# G209B.net
KiCad netlist of a schematic drawn in EAGLE
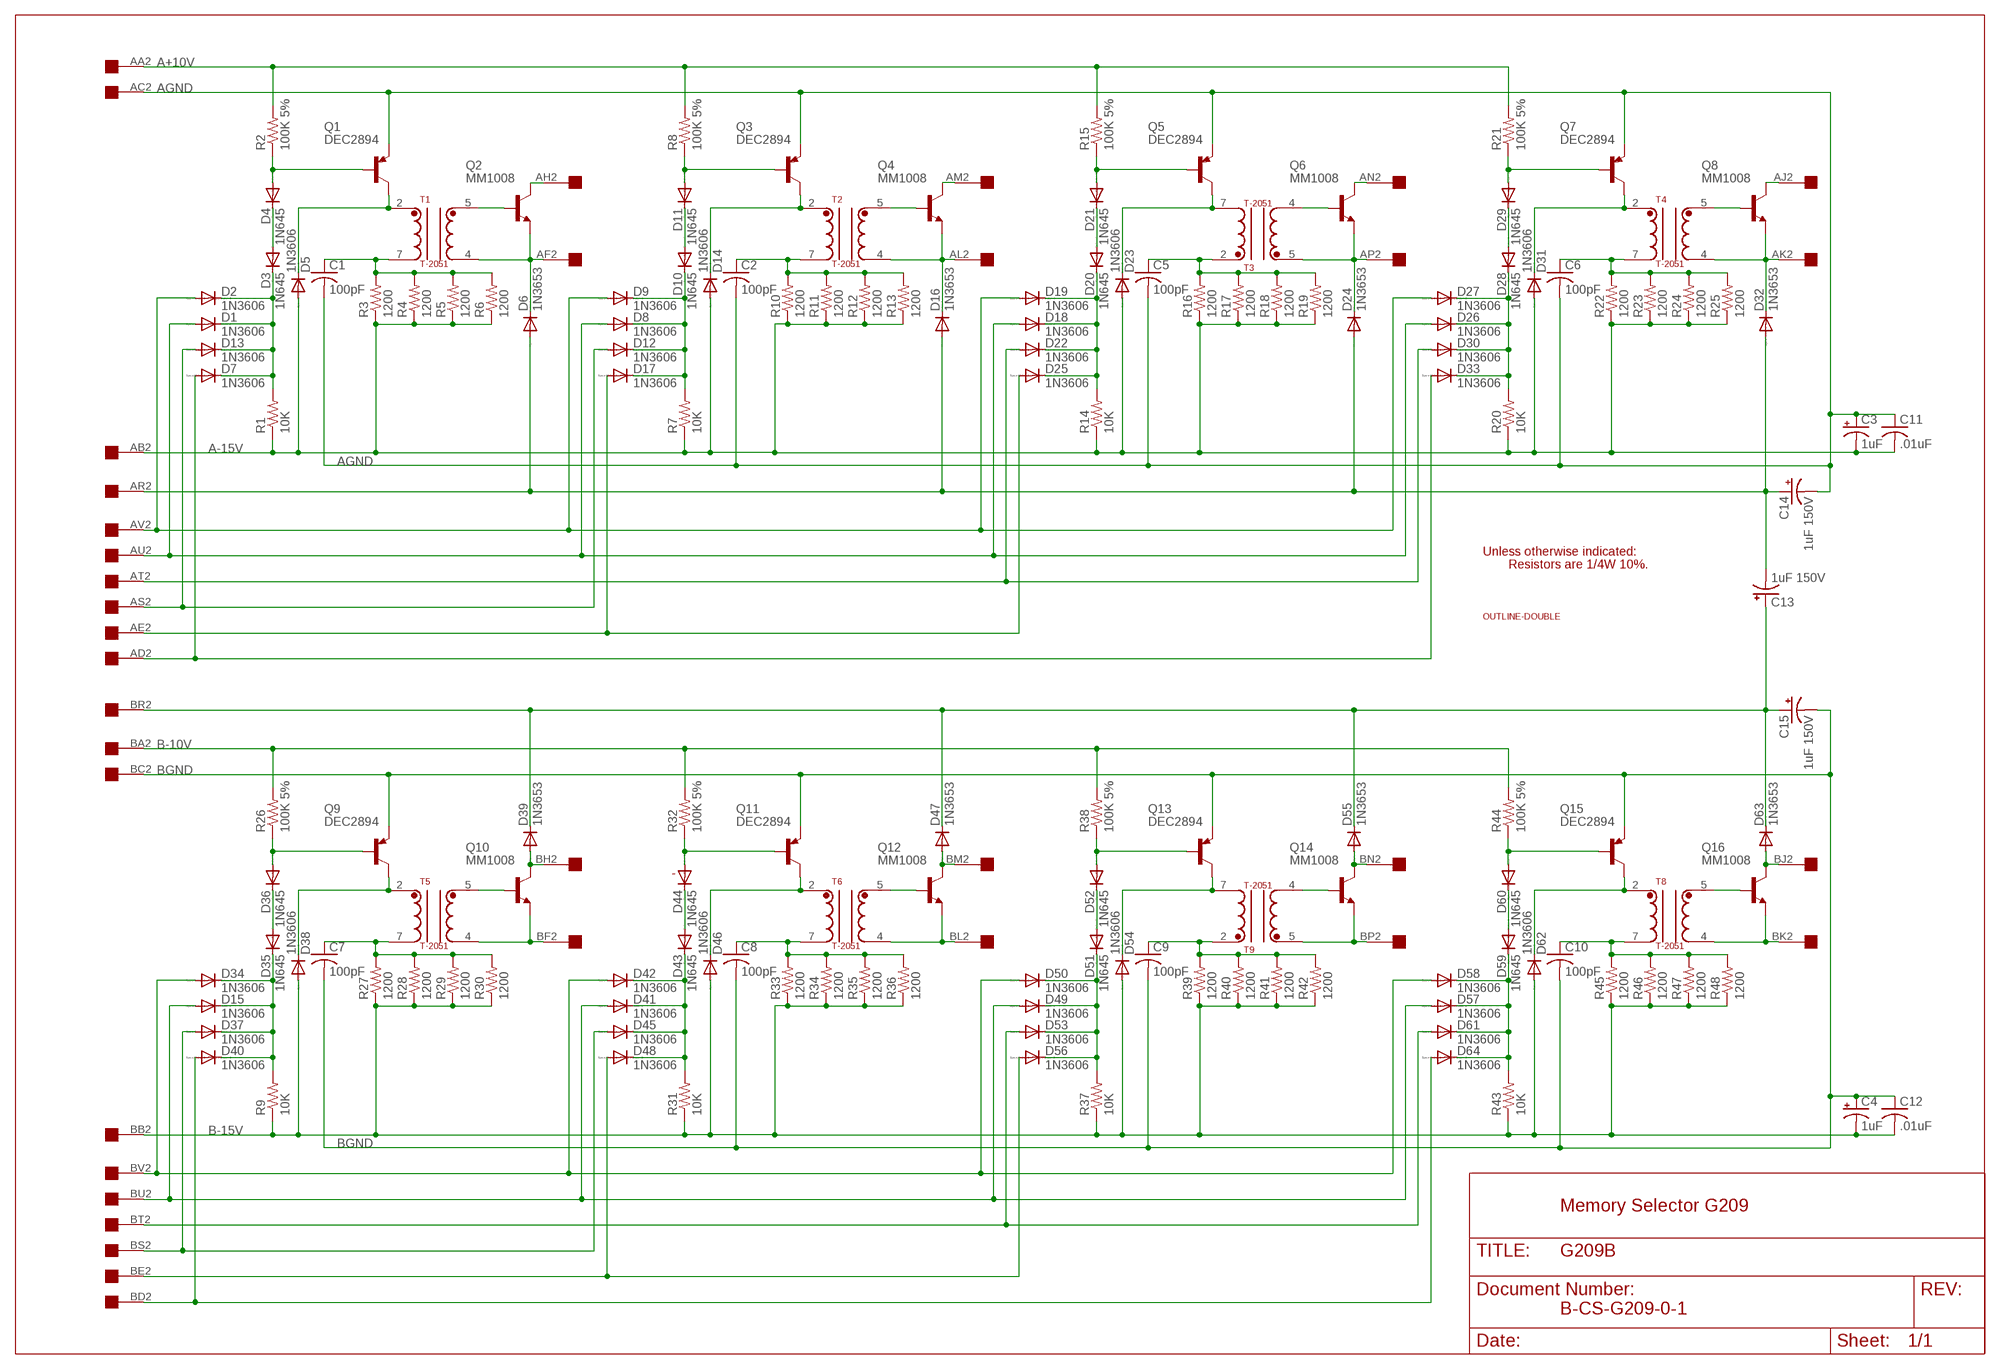
[diagram p0: schematic, sheet 1]

(export (version "E")
  (design (tool "Eeschema 10.0.6"))
  (components
    (comp (ref "C1")
      (value "100pF")
      (footprint "eagle-import:C075-032X103")
      (libsource (lib "eagle-import") (part "C-US075-032X103"))
    )
    (comp (ref "C2")
      (value "100pF")
      (footprint "eagle-import:C075-032X103")
      (libsource (lib "eagle-import") (part "C-US075-032X103"))
    )
    (comp (ref "C3")
      (value "1uF")
      (footprint "eagle-import:E12-4")
      (libsource (lib "eagle-import") (part "CPOL-USE12-4AXIAL"))
    )
    (comp (ref "C4")
      (value "1uF")
      (footprint "eagle-import:E12-4")
      (libsource (lib "eagle-import") (part "CPOL-USE12-4AXIAL"))
    )
    (comp (ref "C5")
      (value "100pF")
      (footprint "eagle-import:C075-032X103")
      (libsource (lib "eagle-import") (part "C-US075-032X103"))
    )
    (comp (ref "C6")
      (value "100pF")
      (footprint "eagle-import:C075-032X103")
      (libsource (lib "eagle-import") (part "C-US075-032X103"))
    )
    (comp (ref "C7")
      (value "100pF")
      (footprint "eagle-import:C075-032X103")
      (libsource (lib "eagle-import") (part "C-US075-032X103"))
    )
    (comp (ref "C8")
      (value "100pF")
      (footprint "eagle-import:C075-032X103")
      (libsource (lib "eagle-import") (part "C-US075-032X103"))
    )
    (comp (ref "C9")
      (value "100pF")
      (footprint "eagle-import:C075-032X103")
      (libsource (lib "eagle-import") (part "C-US075-032X103"))
    )
    (comp (ref "C10")
      (value "100pF")
      (footprint "eagle-import:C075-032X103")
      (libsource (lib "eagle-import") (part "C-US075-032X103"))
    )
    (comp (ref "C11")
      (value ".01uF")
      (footprint "eagle-import:C050-025X075")
      (libsource (lib "eagle-import") (part "C-US050-025X075"))
    )
    (comp (ref "C12")
      (value ".01uF")
      (footprint "eagle-import:C050-025X075")
      (libsource (lib "eagle-import") (part "C-US050-025X075"))
    )
    (comp (ref "C13")
      (value "1uF 150V")
      (footprint "eagle-import:E25-9")
      (libsource (lib "eagle-import") (part "CPOL-USE25-9AXIAL"))
    )
    (comp (ref "C14")
      (value "1uF 150V")
      (footprint "eagle-import:E25-9")
      (libsource (lib "eagle-import") (part "CPOL-USE25-9AXIAL"))
    )
    (comp (ref "C15")
      (value "1uF 150V")
      (footprint "eagle-import:E25-9")
      (libsource (lib "eagle-import") (part "CPOL-USE25-9AXIAL"))
    )
    (comp (ref "D1")
      (value "1N3606")
      (footprint "eagle-import:DO35-10")
      (libsource (lib "eagle-import") (part "1N4148DO35-10"))
    )
    (comp (ref "D2")
      (value "1N3606")
      (footprint "eagle-import:DO35-10")
      (libsource (lib "eagle-import") (part "1N4148DO35-10"))
    )
    (comp (ref "D3")
      (value "1N645")
      (footprint "eagle-import:DO35-10")
      (libsource (lib "eagle-import") (part "1N4148DO35-10"))
    )
    (comp (ref "D4")
      (value "1N645")
      (footprint "eagle-import:DO35-10")
      (libsource (lib "eagle-import") (part "1N4148DO35-10"))
    )
    (comp (ref "D5")
      (value "1N3606")
      (footprint "eagle-import:DO35-10")
      (libsource (lib "eagle-import") (part "1N4148DO35-10"))
    )
    (comp (ref "D6")
      (value "1N3653")
      (footprint "eagle-import:DO35-10")
      (libsource (lib "eagle-import") (part "1N4148DO35-10"))
    )
    (comp (ref "D7")
      (value "1N3606")
      (footprint "eagle-import:DO35-10")
      (libsource (lib "eagle-import") (part "1N4148DO35-10"))
    )
    (comp (ref "D8")
      (value "1N3606")
      (footprint "eagle-import:DO35-10")
      (libsource (lib "eagle-import") (part "1N4148DO35-10"))
    )
    (comp (ref "D9")
      (value "1N3606")
      (footprint "eagle-import:DO35-10")
      (libsource (lib "eagle-import") (part "1N4148DO35-10"))
    )
    (comp (ref "D10")
      (value "1N645")
      (footprint "eagle-import:DO35-10")
      (libsource (lib "eagle-import") (part "1N4148DO35-10"))
    )
    (comp (ref "D11")
      (value "1N645")
      (footprint "eagle-import:DO35-10")
      (libsource (lib "eagle-import") (part "1N4148DO35-10"))
    )
    (comp (ref "D12")
      (value "1N3606")
      (footprint "eagle-import:DO35-10")
      (libsource (lib "eagle-import") (part "1N4148DO35-10"))
    )
    (comp (ref "D13")
      (value "1N3606")
      (footprint "eagle-import:DO35-10")
      (libsource (lib "eagle-import") (part "1N4148DO35-10"))
    )
    (comp (ref "D14")
      (value "1N3606")
      (footprint "eagle-import:DO35-10")
      (libsource (lib "eagle-import") (part "1N4148DO35-10"))
    )
    (comp (ref "D15")
      (value "1N3606")
      (footprint "eagle-import:DO35-10")
      (libsource (lib "eagle-import") (part "1N4148DO35-10"))
    )
    (comp (ref "D16")
      (value "1N3653")
      (footprint "eagle-import:DO35-10")
      (libsource (lib "eagle-import") (part "1N4148DO35-10"))
    )
    (comp (ref "D17")
      (value "1N3606")
      (footprint "eagle-import:DO35-10")
      (libsource (lib "eagle-import") (part "1N4148DO35-10"))
    )
    (comp (ref "D18")
      (value "1N3606")
      (footprint "eagle-import:DO35-10")
      (libsource (lib "eagle-import") (part "1N4148DO35-10"))
    )
    (comp (ref "D19")
      (value "1N3606")
      (footprint "eagle-import:DO35-10")
      (libsource (lib "eagle-import") (part "1N4148DO35-10"))
    )
    (comp (ref "D20")
      (value "1N645")
      (footprint "eagle-import:DO35-10")
      (libsource (lib "eagle-import") (part "1N4148DO35-10"))
    )
    (comp (ref "D21")
      (value "1N645")
      (footprint "eagle-import:DO35-10")
      (libsource (lib "eagle-import") (part "1N4148DO35-10"))
    )
    (comp (ref "D22")
      (value "1N3606")
      (footprint "eagle-import:DO35-10")
      (libsource (lib "eagle-import") (part "1N4148DO35-10"))
    )
    (comp (ref "D23")
      (value "1N3606")
      (footprint "eagle-import:DO35-10")
      (libsource (lib "eagle-import") (part "1N4148DO35-10"))
    )
    (comp (ref "D24")
      (value "1N3653")
      (footprint "eagle-import:DO35-10")
      (libsource (lib "eagle-import") (part "1N4148DO35-10"))
    )
    (comp (ref "D25")
      (value "1N3606")
      (footprint "eagle-import:DO35-10")
      (libsource (lib "eagle-import") (part "1N4148DO35-10"))
    )
    (comp (ref "D26")
      (value "1N3606")
      (footprint "eagle-import:DO35-10")
      (libsource (lib "eagle-import") (part "1N4148DO35-10"))
    )
    (comp (ref "D27")
      (value "1N3606")
      (footprint "eagle-import:DO35-10")
      (libsource (lib "eagle-import") (part "1N4148DO35-10"))
    )
    (comp (ref "D28")
      (value "1N645")
      (footprint "eagle-import:DO35-10")
      (libsource (lib "eagle-import") (part "1N4148DO35-10"))
    )
    (comp (ref "D29")
      (value "1N645")
      (footprint "eagle-import:DO35-10")
      (libsource (lib "eagle-import") (part "1N4148DO35-10"))
    )
    (comp (ref "D30")
      (value "1N3606")
      (footprint "eagle-import:DO35-10")
      (libsource (lib "eagle-import") (part "1N4148DO35-10"))
    )
    (comp (ref "D31")
      (value "1N3606")
      (footprint "eagle-import:DO35-10")
      (libsource (lib "eagle-import") (part "1N4148DO35-10"))
    )
    (comp (ref "D32")
      (value "1N3653")
      (footprint "eagle-import:DO35-10")
      (libsource (lib "eagle-import") (part "1N4148DO35-10"))
    )
    (comp (ref "D33")
      (value "1N3606")
      (footprint "eagle-import:DO35-10")
      (libsource (lib "eagle-import") (part "1N4148DO35-10"))
    )
    (comp (ref "D34")
      (value "1N3606")
      (footprint "eagle-import:DO35-10")
      (libsource (lib "eagle-import") (part "1N4148DO35-10"))
    )
    (comp (ref "D35")
      (value "1N645")
      (footprint "eagle-import:DO35-10")
      (libsource (lib "eagle-import") (part "1N4148DO35-10"))
    )
    (comp (ref "D36")
      (value "1N645")
      (footprint "eagle-import:DO35-10")
      (libsource (lib "eagle-import") (part "1N4148DO35-10"))
    )
    (comp (ref "D37")
      (value "1N3606")
      (footprint "eagle-import:DO35-10")
      (libsource (lib "eagle-import") (part "1N4148DO35-10"))
    )
    (comp (ref "D38")
      (value "1N3606")
      (footprint "eagle-import:DO35-10")
      (libsource (lib "eagle-import") (part "1N4148DO35-10"))
    )
    (comp (ref "D39")
      (value "1N3653")
      (footprint "eagle-import:DO35-10")
      (libsource (lib "eagle-import") (part "1N4148DO35-10"))
    )
    (comp (ref "D40")
      (value "1N3606")
      (footprint "eagle-import:DO35-10")
      (libsource (lib "eagle-import") (part "1N4148DO35-10"))
    )
    (comp (ref "D41")
      (value "1N3606")
      (footprint "eagle-import:DO35-10")
      (libsource (lib "eagle-import") (part "1N4148DO35-10"))
    )
    (comp (ref "D42")
      (value "1N3606")
      (footprint "eagle-import:DO35-10")
      (libsource (lib "eagle-import") (part "1N4148DO35-10"))
    )
    (comp (ref "D43")
      (value "1N645")
      (footprint "eagle-import:DO35-10")
      (libsource (lib "eagle-import") (part "1N4148DO35-10"))
    )
    (comp (ref "D44")
      (value "1N645")
      (footprint "eagle-import:DO35-10")
      (libsource (lib "eagle-import") (part "1N4148DO35-10"))
    )
    (comp (ref "D45")
      (value "1N3606")
      (footprint "eagle-import:DO35-10")
      (libsource (lib "eagle-import") (part "1N4148DO35-10"))
    )
    (comp (ref "D46")
      (value "1N3606")
      (footprint "eagle-import:DO35-10")
      (libsource (lib "eagle-import") (part "1N4148DO35-10"))
    )
    (comp (ref "D47")
      (value "1N3653")
      (footprint "eagle-import:DO35-10")
      (libsource (lib "eagle-import") (part "1N4148DO35-10"))
    )
    (comp (ref "D48")
      (value "1N3606")
      (footprint "eagle-import:DO35-10")
      (libsource (lib "eagle-import") (part "1N4148DO35-10"))
    )
    (comp (ref "D49")
      (value "1N3606")
      (footprint "eagle-import:DO35-10")
      (libsource (lib "eagle-import") (part "1N4148DO35-10"))
    )
    (comp (ref "D50")
      (value "1N3606")
      (footprint "eagle-import:DO35-10")
      (libsource (lib "eagle-import") (part "1N4148DO35-10"))
    )
    (comp (ref "D51")
      (value "1N645")
      (footprint "eagle-import:DO35-10")
      (libsource (lib "eagle-import") (part "1N4148DO35-10"))
    )
    (comp (ref "D52")
      (value "1N645")
      (footprint "eagle-import:DO35-10")
      (libsource (lib "eagle-import") (part "1N4148DO35-10"))
    )
    (comp (ref "D53")
      (value "1N3606")
      (footprint "eagle-import:DO35-10")
      (libsource (lib "eagle-import") (part "1N4148DO35-10"))
    )
    (comp (ref "D54")
      (value "1N3606")
      (footprint "eagle-import:DO35-10")
      (libsource (lib "eagle-import") (part "1N4148DO35-10"))
    )
    (comp (ref "D55")
      (value "1N3653")
      (footprint "eagle-import:DO35-10")
      (libsource (lib "eagle-import") (part "1N4148DO35-10"))
    )
    (comp (ref "D56")
      (value "1N3606")
      (footprint "eagle-import:DO35-10")
      (libsource (lib "eagle-import") (part "1N4148DO35-10"))
    )
    (comp (ref "D57")
      (value "1N3606")
      (footprint "eagle-import:DO35-10")
      (libsource (lib "eagle-import") (part "1N4148DO35-10"))
    )
    (comp (ref "D58")
      (value "1N3606")
      (footprint "eagle-import:DO35-10")
      (libsource (lib "eagle-import") (part "1N4148DO35-10"))
    )
    (comp (ref "D59")
      (value "1N645")
      (footprint "eagle-import:DO35-10")
      (libsource (lib "eagle-import") (part "1N4148DO35-10"))
    )
    (comp (ref "D60")
      (value "1N645")
      (footprint "eagle-import:DO35-10")
      (libsource (lib "eagle-import") (part "1N4148DO35-10"))
    )
    (comp (ref "D61")
      (value "1N3606")
      (footprint "eagle-import:DO35-10")
      (libsource (lib "eagle-import") (part "1N4148DO35-10"))
    )
    (comp (ref "D62")
      (value "1N3606")
      (footprint "eagle-import:DO35-10")
      (libsource (lib "eagle-import") (part "1N4148DO35-10"))
    )
    (comp (ref "D63")
      (value "1N3653")
      (footprint "eagle-import:DO35-10")
      (libsource (lib "eagle-import") (part "1N4148DO35-10"))
    )
    (comp (ref "D64")
      (value "1N3606")
      (footprint "eagle-import:DO35-10")
      (libsource (lib "eagle-import") (part "1N4148DO35-10"))
    )
    (comp (ref "Q1")
      (value "DEC2894")
      (footprint "eagle-import:TO39")
      (libsource (lib "eagle-import") (part "2N2904"))
    )
    (comp (ref "Q2")
      (value "MM1008")
      (footprint "eagle-import:TO5")
      (libsource (lib "eagle-import") (part "2N2102"))
    )
    (comp (ref "Q3")
      (value "DEC2894")
      (footprint "eagle-import:TO39")
      (libsource (lib "eagle-import") (part "2N2904"))
    )
    (comp (ref "Q4")
      (value "MM1008")
      (footprint "eagle-import:TO5")
      (libsource (lib "eagle-import") (part "2N2102"))
    )
    (comp (ref "Q5")
      (value "DEC2894")
      (footprint "eagle-import:TO39")
      (libsource (lib "eagle-import") (part "2N2904"))
    )
    (comp (ref "Q6")
      (value "MM1008")
      (footprint "eagle-import:TO5")
      (libsource (lib "eagle-import") (part "2N2102"))
    )
    (comp (ref "Q7")
      (value "DEC2894")
      (footprint "eagle-import:TO39")
      (libsource (lib "eagle-import") (part "2N2904"))
    )
    (comp (ref "Q8")
      (value "MM1008")
      (footprint "eagle-import:TO5")
      (libsource (lib "eagle-import") (part "2N2102"))
    )
    (comp (ref "Q9")
      (value "DEC2894")
      (footprint "eagle-import:TO39")
      (libsource (lib "eagle-import") (part "2N2904"))
    )
    (comp (ref "Q10")
      (value "MM1008")
      (footprint "eagle-import:TO5")
      (libsource (lib "eagle-import") (part "2N2102"))
    )
    (comp (ref "Q11")
      (value "DEC2894")
      (footprint "eagle-import:TO39")
      (libsource (lib "eagle-import") (part "2N2904"))
    )
    (comp (ref "Q12")
      (value "MM1008")
      (footprint "eagle-import:TO5")
      (libsource (lib "eagle-import") (part "2N2102"))
    )
    (comp (ref "Q13")
      (value "DEC2894")
      (footprint "eagle-import:TO39")
      (libsource (lib "eagle-import") (part "2N2904"))
    )
    (comp (ref "Q14")
      (value "MM1008")
      (footprint "eagle-import:TO5")
      (libsource (lib "eagle-import") (part "2N2102"))
    )
    (comp (ref "Q15")
      (value "DEC2894")
      (footprint "eagle-import:TO39")
      (libsource (lib "eagle-import") (part "2N2904"))
    )
    (comp (ref "Q16")
      (value "MM1008")
      (footprint "eagle-import:TO5")
      (libsource (lib "eagle-import") (part "2N2102"))
    )
    (comp (ref "R1")
      (value "10K")
      (footprint "eagle-import:0207_10")
      (libsource (lib "eagle-import") (part "R-US_0207/10"))
    )
    (comp (ref "R2")
      (value "100K 5%")
      (footprint "eagle-import:0207_10")
      (libsource (lib "eagle-import") (part "R-US_0207/10"))
    )
    (comp (ref "R3")
      (value "1200")
      (footprint "eagle-import:0207_10")
      (libsource (lib "eagle-import") (part "R-US_0207/10"))
    )
    (comp (ref "R4")
      (value "1200")
      (footprint "eagle-import:0207_10")
      (libsource (lib "eagle-import") (part "R-US_0207/10"))
    )
    (comp (ref "R5")
      (value "1200")
      (footprint "eagle-import:0207_10")
      (libsource (lib "eagle-import") (part "R-US_0207/10"))
    )
    (comp (ref "R6")
      (value "1200")
      (footprint "eagle-import:0207_10")
      (libsource (lib "eagle-import") (part "R-US_0207/10"))
    )
    (comp (ref "R7")
      (value "10K")
      (footprint "eagle-import:0207_10")
      (libsource (lib "eagle-import") (part "R-US_0207/10"))
    )
    (comp (ref "R8")
      (value "100K 5%")
      (footprint "eagle-import:0207_10")
      (libsource (lib "eagle-import") (part "R-US_0207/10"))
    )
    (comp (ref "R9")
      (value "10K")
      (footprint "eagle-import:0207_10")
      (libsource (lib "eagle-import") (part "R-US_0207/10"))
    )
    (comp (ref "R10")
      (value "1200")
      (footprint "eagle-import:0207_10")
      (libsource (lib "eagle-import") (part "R-US_0207/10"))
    )
    (comp (ref "R11")
      (value "1200")
      (footprint "eagle-import:0207_10")
      (libsource (lib "eagle-import") (part "R-US_0207/10"))
    )
    (comp (ref "R12")
      (value "1200")
      (footprint "eagle-import:0207_10")
      (libsource (lib "eagle-import") (part "R-US_0207/10"))
    )
    (comp (ref "R13")
      (value "1200")
      (footprint "eagle-import:0207_10")
      (libsource (lib "eagle-import") (part "R-US_0207/10"))
    )
    (comp (ref "R14")
      (value "10K")
      (footprint "eagle-import:0207_10")
      (libsource (lib "eagle-import") (part "R-US_0207/10"))
    )
    (comp (ref "R15")
      (value "100K 5%")
      (footprint "eagle-import:0207_10")
      (libsource (lib "eagle-import") (part "R-US_0207/10"))
    )
    (comp (ref "R16")
      (value "1200")
      (footprint "eagle-import:0207_10")
      (libsource (lib "eagle-import") (part "R-US_0207/10"))
    )
    (comp (ref "R17")
      (value "1200")
      (footprint "eagle-import:0207_10")
      (libsource (lib "eagle-import") (part "R-US_0207/10"))
    )
    (comp (ref "R18")
      (value "1200")
      (footprint "eagle-import:0207_10")
      (libsource (lib "eagle-import") (part "R-US_0207/10"))
    )
    (comp (ref "R19")
      (value "1200")
      (footprint "eagle-import:0207_10")
      (libsource (lib "eagle-import") (part "R-US_0207/10"))
    )
    (comp (ref "R20")
      (value "10K")
      (footprint "eagle-import:0207_10")
      (libsource (lib "eagle-import") (part "R-US_0207/10"))
    )
    (comp (ref "R21")
      (value "100K 5%")
      (footprint "eagle-import:0207_10")
      (libsource (lib "eagle-import") (part "R-US_0207/10"))
    )
    (comp (ref "R22")
      (value "1200")
      (footprint "eagle-import:0207_10")
      (libsource (lib "eagle-import") (part "R-US_0207/10"))
    )
    (comp (ref "R23")
      (value "1200")
      (footprint "eagle-import:0207_10")
      (libsource (lib "eagle-import") (part "R-US_0207/10"))
    )
    (comp (ref "R24")
      (value "1200")
      (footprint "eagle-import:0207_10")
      (libsource (lib "eagle-import") (part "R-US_0207/10"))
    )
    (comp (ref "R25")
      (value "1200")
      (footprint "eagle-import:0207_10")
      (libsource (lib "eagle-import") (part "R-US_0207/10"))
    )
    (comp (ref "R26")
      (value "100K 5%")
      (footprint "eagle-import:0207_10")
      (libsource (lib "eagle-import") (part "R-US_0207/10"))
    )
    (comp (ref "R27")
      (value "1200")
      (footprint "eagle-import:0207_10")
      (libsource (lib "eagle-import") (part "R-US_0207/10"))
    )
    (comp (ref "R28")
      (value "1200")
      (footprint "eagle-import:0207_10")
      (libsource (lib "eagle-import") (part "R-US_0207/10"))
    )
    (comp (ref "R29")
      (value "1200")
      (footprint "eagle-import:0207_10")
      (libsource (lib "eagle-import") (part "R-US_0207/10"))
    )
    (comp (ref "R30")
      (value "1200")
      (footprint "eagle-import:0207_10")
      (libsource (lib "eagle-import") (part "R-US_0207/10"))
    )
    (comp (ref "R31")
      (value "10K")
      (footprint "eagle-import:0207_10")
      (libsource (lib "eagle-import") (part "R-US_0207/10"))
    )
    (comp (ref "R32")
      (value "100K 5%")
      (footprint "eagle-import:0207_10")
      (libsource (lib "eagle-import") (part "R-US_0207/10"))
    )
    (comp (ref "R33")
      (value "1200")
      (footprint "eagle-import:0207_10")
      (libsource (lib "eagle-import") (part "R-US_0207/10"))
    )
    (comp (ref "R34")
      (value "1200")
      (footprint "eagle-import:0207_10")
      (libsource (lib "eagle-import") (part "R-US_0207/10"))
    )
    (comp (ref "R35")
      (value "1200")
      (footprint "eagle-import:0207_10")
      (libsource (lib "eagle-import") (part "R-US_0207/10"))
    )
    (comp (ref "R36")
      (value "1200")
      (footprint "eagle-import:0207_10")
      (libsource (lib "eagle-import") (part "R-US_0207/10"))
    )
    (comp (ref "R37")
      (value "10K")
      (footprint "eagle-import:0207_10")
      (libsource (lib "eagle-import") (part "R-US_0207/10"))
    )
    (comp (ref "R38")
      (value "100K 5%")
      (footprint "eagle-import:0207_10")
      (libsource (lib "eagle-import") (part "R-US_0207/10"))
    )
    (comp (ref "R39")
      (value "1200")
      (footprint "eagle-import:0207_10")
      (libsource (lib "eagle-import") (part "R-US_0207/10"))
    )
    (comp (ref "R40")
      (value "1200")
      (footprint "eagle-import:0207_10")
      (libsource (lib "eagle-import") (part "R-US_0207/10"))
    )
    (comp (ref "R41")
      (value "1200")
      (footprint "eagle-import:0207_10")
      (libsource (lib "eagle-import") (part "R-US_0207/10"))
    )
    (comp (ref "R42")
      (value "1200")
      (footprint "eagle-import:0207_10")
      (libsource (lib "eagle-import") (part "R-US_0207/10"))
    )
    (comp (ref "R43")
      (value "10K")
      (footprint "eagle-import:0207_10")
      (libsource (lib "eagle-import") (part "R-US_0207/10"))
    )
    (comp (ref "R44")
      (value "100K 5%")
      (footprint "eagle-import:0207_10")
      (libsource (lib "eagle-import") (part "R-US_0207/10"))
    )
    (comp (ref "R45")
      (value "1200")
      (footprint "eagle-import:0207_10")
      (libsource (lib "eagle-import") (part "R-US_0207/10"))
    )
    (comp (ref "R46")
      (value "1200")
      (footprint "eagle-import:0207_10")
      (libsource (lib "eagle-import") (part "R-US_0207/10"))
    )
    (comp (ref "R47")
      (value "1200")
      (footprint "eagle-import:0207_10")
      (libsource (lib "eagle-import") (part "R-US_0207/10"))
    )
    (comp (ref "R48")
      (value "1200")
      (footprint "eagle-import:0207_10")
      (libsource (lib "eagle-import") (part "R-US_0207/10"))
    )
    (comp (ref "T1")
      (value "T-2051")
      (footprint "eagle-import:TRANSFORMER")
      (libsource (lib "eagle-import") (part "T-2051"))
    )
    (comp (ref "T2")
      (value "T-2051")
      (footprint "eagle-import:TRANSFORMER")
      (libsource (lib "eagle-import") (part "T-2051"))
    )
    (comp (ref "T3")
      (value "T-2051")
      (footprint "eagle-import:TRANSFORMER")
      (libsource (lib "eagle-import") (part "T-2051"))
    )
    (comp (ref "T4")
      (value "T-2051")
      (footprint "eagle-import:TRANSFORMER")
      (libsource (lib "eagle-import") (part "T-2051"))
    )
    (comp (ref "T5")
      (value "T-2051")
      (footprint "eagle-import:TRANSFORMER")
      (libsource (lib "eagle-import") (part "T-2051"))
    )
    (comp (ref "T6")
      (value "T-2051")
      (footprint "eagle-import:TRANSFORMER")
      (libsource (lib "eagle-import") (part "T-2051"))
    )
    (comp (ref "T8")
      (value "T-2051")
      (footprint "eagle-import:TRANSFORMER")
      (libsource (lib "eagle-import") (part "T-2051"))
    )
    (comp (ref "T9")
      (value "T-2051")
      (footprint "eagle-import:TRANSFORMER")
      (libsource (lib "eagle-import") (part "T-2051"))
    )
    (comp (ref "U$1")
      (value "DOUBLE")
      (footprint "eagle-import:EDGE-CON4")
      (libsource (lib "eagle-import") (part "DOUBLE"))
    )
    (comp (ref "U$3")
      (value "OUTLINE-DOUBLE")
      (footprint "eagle-import:DOUBLE")
      (libsource (lib "eagle-import") (part "OUTLINE-DOUBLE"))
    )
  )
  (nets
    (net (code "1") (name "/A+10V") (class "Default")
      (node (ref "R15") (pin "2") (pinfunction "2_2") (pintype "passive"))
      (node (ref "R2") (pin "2") (pinfunction "2_2") (pintype "passive"))
      (node (ref "R21") (pin "2") (pinfunction "2_2") (pintype "passive"))
      (node (ref "R8") (pin "2") (pinfunction "2_2") (pintype "passive"))
      (node (ref "U$1") (pin "AA2") (pinfunction "1_AA2") (pintype "bidirectional"))
    )
    (net (code "2") (name "/A-15V") (class "Default")
      (node (ref "C11") (pin "2") (pinfunction "2_2") (pintype "passive"))
      (node (ref "C3") (pin "-") (pinfunction "-_-") (pintype "passive"))
      (node (ref "D14") (pin "A") (pinfunction "A_A") (pintype "passive"))
      (node (ref "D23") (pin "A") (pinfunction "A_A") (pintype "passive"))
      (node (ref "D31") (pin "A") (pinfunction "A_A") (pintype "passive"))
      (node (ref "D5") (pin "A") (pinfunction "A_A") (pintype "passive"))
      (node (ref "R1") (pin "1") (pinfunction "1_1") (pintype "passive"))
      (node (ref "R10") (pin "1") (pinfunction "1_1") (pintype "passive"))
      (node (ref "R11") (pin "1") (pinfunction "1_1") (pintype "passive"))
      (node (ref "R12") (pin "1") (pinfunction "1_1") (pintype "passive"))
      (node (ref "R13") (pin "1") (pinfunction "1_1") (pintype "passive"))
      (node (ref "R14") (pin "1") (pinfunction "1_1") (pintype "passive"))
      (node (ref "R16") (pin "1") (pinfunction "1_1") (pintype "passive"))
      (node (ref "R17") (pin "1") (pinfunction "1_1") (pintype "passive"))
      (node (ref "R18") (pin "1") (pinfunction "1_1") (pintype "passive"))
      (node (ref "R19") (pin "1") (pinfunction "1_1") (pintype "passive"))
      (node (ref "R20") (pin "1") (pinfunction "1_1") (pintype "passive"))
      (node (ref "R22") (pin "1") (pinfunction "1_1") (pintype "passive"))
      (node (ref "R23") (pin "1") (pinfunction "1_1") (pintype "passive"))
      (node (ref "R24") (pin "1") (pinfunction "1_1") (pintype "passive"))
      (node (ref "R25") (pin "1") (pinfunction "1_1") (pintype "passive"))
      (node (ref "R3") (pin "1") (pinfunction "1_1") (pintype "passive"))
      (node (ref "R4") (pin "1") (pinfunction "1_1") (pintype "passive"))
      (node (ref "R5") (pin "1") (pinfunction "1_1") (pintype "passive"))
      (node (ref "R6") (pin "1") (pinfunction "1_1") (pintype "passive"))
      (node (ref "R7") (pin "1") (pinfunction "1_1") (pintype "passive"))
      (node (ref "U$1") (pin "AB2") (pinfunction "1_AB2") (pintype "bidirectional"))
    )
    (net (code "3") (name "/AGND") (class "Default")
      (node (ref "C1") (pin "2") (pinfunction "2_2") (pintype "passive"))
      (node (ref "C11") (pin "1") (pinfunction "1_1") (pintype "passive"))
      (node (ref "C14") (pin "-") (pinfunction "-_-") (pintype "passive"))
      (node (ref "C2") (pin "2") (pinfunction "2_2") (pintype "passive"))
      (node (ref "C3") (pin "+") (pinfunction "+_+") (pintype "passive"))
      (node (ref "C5") (pin "2") (pinfunction "2_2") (pintype "passive"))
      (node (ref "C6") (pin "2") (pinfunction "2_2") (pintype "passive"))
      (node (ref "Q1") (pin "1") (pinfunction "E_1") (pintype "passive"))
      (node (ref "Q3") (pin "1") (pinfunction "E_1") (pintype "passive"))
      (node (ref "Q5") (pin "1") (pinfunction "E_1") (pintype "passive"))
      (node (ref "Q7") (pin "1") (pinfunction "E_1") (pintype "passive"))
      (node (ref "U$1") (pin "AC2") (pinfunction "1_AC2") (pintype "bidirectional"))
    )
    (net (code "4") (name "/B-10V") (class "Default")
      (node (ref "R26") (pin "2") (pinfunction "2_2") (pintype "passive"))
      (node (ref "R32") (pin "2") (pinfunction "2_2") (pintype "passive"))
      (node (ref "R38") (pin "2") (pinfunction "2_2") (pintype "passive"))
      (node (ref "R44") (pin "2") (pinfunction "2_2") (pintype "passive"))
      (node (ref "U$1") (pin "BA2") (pinfunction "1_BA2") (pintype "bidirectional"))
    )
    (net (code "5") (name "/B-15V") (class "Default")
      (node (ref "C12") (pin "2") (pinfunction "2_2") (pintype "passive"))
      (node (ref "C4") (pin "-") (pinfunction "-_-") (pintype "passive"))
      (node (ref "D38") (pin "A") (pinfunction "A_A") (pintype "passive"))
      (node (ref "D46") (pin "A") (pinfunction "A_A") (pintype "passive"))
      (node (ref "D54") (pin "A") (pinfunction "A_A") (pintype "passive"))
      (node (ref "D62") (pin "A") (pinfunction "A_A") (pintype "passive"))
      (node (ref "R27") (pin "1") (pinfunction "1_1") (pintype "passive"))
      (node (ref "R28") (pin "1") (pinfunction "1_1") (pintype "passive"))
      (node (ref "R29") (pin "1") (pinfunction "1_1") (pintype "passive"))
      (node (ref "R30") (pin "1") (pinfunction "1_1") (pintype "passive"))
      (node (ref "R31") (pin "1") (pinfunction "1_1") (pintype "passive"))
      (node (ref "R33") (pin "1") (pinfunction "1_1") (pintype "passive"))
      (node (ref "R34") (pin "1") (pinfunction "1_1") (pintype "passive"))
      (node (ref "R35") (pin "1") (pinfunction "1_1") (pintype "passive"))
      (node (ref "R36") (pin "1") (pinfunction "1_1") (pintype "passive"))
      (node (ref "R37") (pin "1") (pinfunction "1_1") (pintype "passive"))
      (node (ref "R39") (pin "1") (pinfunction "1_1") (pintype "passive"))
      (node (ref "R40") (pin "1") (pinfunction "1_1") (pintype "passive"))
      (node (ref "R41") (pin "1") (pinfunction "1_1") (pintype "passive"))
      (node (ref "R42") (pin "1") (pinfunction "1_1") (pintype "passive"))
      (node (ref "R43") (pin "1") (pinfunction "1_1") (pintype "passive"))
      (node (ref "R45") (pin "1") (pinfunction "1_1") (pintype "passive"))
      (node (ref "R46") (pin "1") (pinfunction "1_1") (pintype "passive"))
      (node (ref "R47") (pin "1") (pinfunction "1_1") (pintype "passive"))
      (node (ref "R48") (pin "1") (pinfunction "1_1") (pintype "passive"))
      (node (ref "R9") (pin "1") (pinfunction "1_1") (pintype "passive"))
      (node (ref "U$1") (pin "BB2") (pinfunction "1_BB2") (pintype "bidirectional"))
    )
    (net (code "6") (name "/BGND") (class "Default")
      (node (ref "C10") (pin "2") (pinfunction "2_2") (pintype "passive"))
      (node (ref "C12") (pin "1") (pinfunction "1_1") (pintype "passive"))
      (node (ref "C15") (pin "-") (pinfunction "-_-") (pintype "passive"))
      (node (ref "C4") (pin "+") (pinfunction "+_+") (pintype "passive"))
      (node (ref "C7") (pin "2") (pinfunction "2_2") (pintype "passive"))
      (node (ref "C8") (pin "2") (pinfunction "2_2") (pintype "passive"))
      (node (ref "C9") (pin "2") (pinfunction "2_2") (pintype "passive"))
      (node (ref "Q11") (pin "1") (pinfunction "E_1") (pintype "passive"))
      (node (ref "Q13") (pin "1") (pinfunction "E_1") (pintype "passive"))
      (node (ref "Q15") (pin "1") (pinfunction "E_1") (pintype "passive"))
      (node (ref "Q9") (pin "1") (pinfunction "E_1") (pintype "passive"))
      (node (ref "U$1") (pin "BC2") (pinfunction "1_BC2") (pintype "bidirectional"))
    )
    (net (code "7") (name "Net-(D1-PadC)") (class "Default")
      (node (ref "D1") (pin "C") (pinfunction "C_C") (pintype "passive"))
      (node (ref "D13") (pin "C") (pinfunction "C_C") (pintype "passive"))
      (node (ref "D2") (pin "C") (pinfunction "C_C") (pintype "passive"))
      (node (ref "D3") (pin "C") (pinfunction "C_C") (pintype "passive"))
      (node (ref "D7") (pin "C") (pinfunction "C_C") (pintype "passive"))
      (node (ref "R1") (pin "2") (pinfunction "2_2") (pintype "passive"))
    )
    (net (code "8") (name "Net-(D3-PadA)") (class "Default")
      (node (ref "D3") (pin "A") (pinfunction "A_A") (pintype "passive"))
      (node (ref "D4") (pin "C") (pinfunction "C_C") (pintype "passive"))
    )
    (net (code "9") (name "Net-(D10-PadA)") (class "Default")
      (node (ref "D10") (pin "A") (pinfunction "A_A") (pintype "passive"))
      (node (ref "D11") (pin "C") (pinfunction "C_C") (pintype "passive"))
    )
    (net (code "10") (name "Net-(D10-PadC)") (class "Default")
      (node (ref "D10") (pin "C") (pinfunction "C_C") (pintype "passive"))
      (node (ref "D12") (pin "C") (pinfunction "C_C") (pintype "passive"))
      (node (ref "D17") (pin "C") (pinfunction "C_C") (pintype "passive"))
      (node (ref "D8") (pin "C") (pinfunction "C_C") (pintype "passive"))
      (node (ref "D9") (pin "C") (pinfunction "C_C") (pintype "passive"))
      (node (ref "R7") (pin "2") (pinfunction "2_2") (pintype "passive"))
    )
    (net (code "11") (name "Net-(D15-PadC)") (class "Default")
      (node (ref "D15") (pin "C") (pinfunction "C_C") (pintype "passive"))
      (node (ref "D34") (pin "C") (pinfunction "C_C") (pintype "passive"))
      (node (ref "D35") (pin "C") (pinfunction "C_C") (pintype "passive"))
      (node (ref "D37") (pin "C") (pinfunction "C_C") (pintype "passive"))
      (node (ref "D40") (pin "C") (pinfunction "C_C") (pintype "passive"))
      (node (ref "R9") (pin "2") (pinfunction "2_2") (pintype "passive"))
    )
    (net (code "12") (name "Net-(D18-PadC)") (class "Default")
      (node (ref "D18") (pin "C") (pinfunction "C_C") (pintype "passive"))
      (node (ref "D19") (pin "C") (pinfunction "C_C") (pintype "passive"))
      (node (ref "D20") (pin "C") (pinfunction "C_C") (pintype "passive"))
      (node (ref "D22") (pin "C") (pinfunction "C_C") (pintype "passive"))
      (node (ref "D25") (pin "C") (pinfunction "C_C") (pintype "passive"))
      (node (ref "R14") (pin "2") (pinfunction "2_2") (pintype "passive"))
    )
    (net (code "13") (name "Net-(D20-PadA)") (class "Default")
      (node (ref "D20") (pin "A") (pinfunction "A_A") (pintype "passive"))
      (node (ref "D21") (pin "C") (pinfunction "C_C") (pintype "passive"))
    )
    (net (code "14") (name "Net-(D26-PadC)") (class "Default")
      (node (ref "D26") (pin "C") (pinfunction "C_C") (pintype "passive"))
      (node (ref "D27") (pin "C") (pinfunction "C_C") (pintype "passive"))
      (node (ref "D28") (pin "C") (pinfunction "C_C") (pintype "passive"))
      (node (ref "D30") (pin "C") (pinfunction "C_C") (pintype "passive"))
      (node (ref "D33") (pin "C") (pinfunction "C_C") (pintype "passive"))
      (node (ref "R20") (pin "2") (pinfunction "2_2") (pintype "passive"))
    )
    (net (code "15") (name "Net-(D28-PadA)") (class "Default")
      (node (ref "D28") (pin "A") (pinfunction "A_A") (pintype "passive"))
      (node (ref "D29") (pin "C") (pinfunction "C_C") (pintype "passive"))
    )
    (net (code "16") (name "Net-(D35-PadA)") (class "Default")
      (node (ref "D35") (pin "A") (pinfunction "A_A") (pintype "passive"))
      (node (ref "D36") (pin "C") (pinfunction "C_C") (pintype "passive"))
    )
    (net (code "17") (name "Net-(D41-PadC)") (class "Default")
      (node (ref "D41") (pin "C") (pinfunction "C_C") (pintype "passive"))
      (node (ref "D42") (pin "C") (pinfunction "C_C") (pintype "passive"))
      (node (ref "D43") (pin "C") (pinfunction "C_C") (pintype "passive"))
      (node (ref "D45") (pin "C") (pinfunction "C_C") (pintype "passive"))
      (node (ref "D48") (pin "C") (pinfunction "C_C") (pintype "passive"))
      (node (ref "R31") (pin "2") (pinfunction "2_2") (pintype "passive"))
    )
    (net (code "18") (name "Net-(D43-PadA)") (class "Default")
      (node (ref "D43") (pin "A") (pinfunction "A_A") (pintype "passive"))
      (node (ref "D44") (pin "C") (pinfunction "C_C") (pintype "passive"))
    )
    (net (code "19") (name "Net-(D49-PadC)") (class "Default")
      (node (ref "D49") (pin "C") (pinfunction "C_C") (pintype "passive"))
      (node (ref "D50") (pin "C") (pinfunction "C_C") (pintype "passive"))
      (node (ref "D51") (pin "C") (pinfunction "C_C") (pintype "passive"))
      (node (ref "D53") (pin "C") (pinfunction "C_C") (pintype "passive"))
      (node (ref "D56") (pin "C") (pinfunction "C_C") (pintype "passive"))
      (node (ref "R37") (pin "2") (pinfunction "2_2") (pintype "passive"))
    )
    (net (code "20") (name "Net-(D51-PadA)") (class "Default")
      (node (ref "D51") (pin "A") (pinfunction "A_A") (pintype "passive"))
      (node (ref "D52") (pin "C") (pinfunction "C_C") (pintype "passive"))
    )
    (net (code "21") (name "Net-(D57-PadC)") (class "Default")
      (node (ref "D57") (pin "C") (pinfunction "C_C") (pintype "passive"))
      (node (ref "D58") (pin "C") (pinfunction "C_C") (pintype "passive"))
      (node (ref "D59") (pin "C") (pinfunction "C_C") (pintype "passive"))
      (node (ref "D61") (pin "C") (pinfunction "C_C") (pintype "passive"))
      (node (ref "D64") (pin "C") (pinfunction "C_C") (pintype "passive"))
      (node (ref "R43") (pin "2") (pinfunction "2_2") (pintype "passive"))
    )
    (net (code "22") (name "Net-(D59-PadA)") (class "Default")
      (node (ref "D59") (pin "A") (pinfunction "A_A") (pintype "passive"))
      (node (ref "D60") (pin "C") (pinfunction "C_C") (pintype "passive"))
    )
    (net (code "23") (name "Net-(Q1-B)") (class "Default")
      (node (ref "D4") (pin "A") (pinfunction "A_A") (pintype "passive"))
      (node (ref "Q1") (pin "2") (pinfunction "B_2") (pintype "passive"))
      (node (ref "R2") (pin "1") (pinfunction "1_1") (pintype "passive"))
    )
    (net (code "24") (name "Net-(Q1-C)") (class "Default")
      (node (ref "D5") (pin "C") (pinfunction "C_C") (pintype "passive"))
      (node (ref "Q1") (pin "3") (pinfunction "C_3") (pintype "passive"))
      (node (ref "T1") (pin "2") (pinfunction "P$2_2") (pintype "passive"))
    )
    (net (code "25") (name "Net-(Q2-B)") (class "Default")
      (node (ref "Q2") (pin "2") (pinfunction "B_2") (pintype "passive"))
      (node (ref "T1") (pin "5") (pinfunction "P$4_5") (pintype "passive"))
    )
    (net (code "26") (name "Net-(Q2-C)") (class "Default")
      (node (ref "Q2") (pin "3") (pinfunction "C_3") (pintype "passive"))
      (node (ref "U$1") (pin "AH2") (pinfunction "1_AH2") (pintype "bidirectional"))
    )
    (net (code "27") (name "Net-(Q2-E)") (class "Default")
      (node (ref "D6") (pin "C") (pinfunction "C_C") (pintype "passive"))
      (node (ref "Q2") (pin "1") (pinfunction "E_1") (pintype "passive"))
      (node (ref "T1") (pin "4") (pinfunction "P$5_4") (pintype "passive"))
      (node (ref "U$1") (pin "AF2") (pinfunction "1_AF2") (pintype "bidirectional"))
    )
    (net (code "28") (name "Net-(Q3-B)") (class "Default")
      (node (ref "D11") (pin "A") (pinfunction "A_A") (pintype "passive"))
      (node (ref "Q3") (pin "2") (pinfunction "B_2") (pintype "passive"))
      (node (ref "R8") (pin "1") (pinfunction "1_1") (pintype "passive"))
    )
    (net (code "29") (name "Net-(Q3-C)") (class "Default")
      (node (ref "D14") (pin "C") (pinfunction "C_C") (pintype "passive"))
      (node (ref "Q3") (pin "3") (pinfunction "C_3") (pintype "passive"))
      (node (ref "T2") (pin "2") (pinfunction "P$2_2") (pintype "passive"))
    )
    (net (code "30") (name "Net-(Q4-B)") (class "Default")
      (node (ref "Q4") (pin "2") (pinfunction "B_2") (pintype "passive"))
      (node (ref "T2") (pin "5") (pinfunction "P$4_5") (pintype "passive"))
    )
    (net (code "31") (name "Net-(Q4-C)") (class "Default")
      (node (ref "Q4") (pin "3") (pinfunction "C_3") (pintype "passive"))
      (node (ref "U$1") (pin "AM2") (pinfunction "1_AM2") (pintype "bidirectional"))
    )
    (net (code "32") (name "Net-(Q4-E)") (class "Default")
      (node (ref "D16") (pin "C") (pinfunction "C_C") (pintype "passive"))
      (node (ref "Q4") (pin "1") (pinfunction "E_1") (pintype "passive"))
      (node (ref "T2") (pin "4") (pinfunction "P$5_4") (pintype "passive"))
      (node (ref "U$1") (pin "AL2") (pinfunction "1_AL2") (pintype "bidirectional"))
    )
    (net (code "33") (name "Net-(Q5-B)") (class "Default")
      (node (ref "D21") (pin "A") (pinfunction "A_A") (pintype "passive"))
      (node (ref "Q5") (pin "2") (pinfunction "B_2") (pintype "passive"))
      (node (ref "R15") (pin "1") (pinfunction "1_1") (pintype "passive"))
    )
    (net (code "34") (name "Net-(Q5-C)") (class "Default")
      (node (ref "D23") (pin "C") (pinfunction "C_C") (pintype "passive"))
      (node (ref "Q5") (pin "3") (pinfunction "C_3") (pintype "passive"))
      (node (ref "T3") (pin "7") (pinfunction "P$7_7") (pintype "passive"))
    )
    (net (code "35") (name "Net-(Q6-B)") (class "Default")
      (node (ref "Q6") (pin "2") (pinfunction "B_2") (pintype "passive"))
      (node (ref "T3") (pin "4") (pinfunction "P$5_4") (pintype "passive"))
    )
    (net (code "36") (name "Net-(Q6-C)") (class "Default")
      (node (ref "Q6") (pin "3") (pinfunction "C_3") (pintype "passive"))
      (node (ref "U$1") (pin "AN2") (pinfunction "1_AN2") (pintype "bidirectional"))
    )
    (net (code "37") (name "Net-(Q6-E)") (class "Default")
      (node (ref "D24") (pin "C") (pinfunction "C_C") (pintype "passive"))
      (node (ref "Q6") (pin "1") (pinfunction "E_1") (pintype "passive"))
      (node (ref "T3") (pin "5") (pinfunction "P$4_5") (pintype "passive"))
      (node (ref "U$1") (pin "AP2") (pinfunction "1_AP2") (pintype "bidirectional"))
    )
    (net (code "38") (name "Net-(Q7-B)") (class "Default")
      (node (ref "D29") (pin "A") (pinfunction "A_A") (pintype "passive"))
      (node (ref "Q7") (pin "2") (pinfunction "B_2") (pintype "passive"))
      (node (ref "R21") (pin "1") (pinfunction "1_1") (pintype "passive"))
    )
    (net (code "39") (name "Net-(Q7-C)") (class "Default")
      (node (ref "D31") (pin "C") (pinfunction "C_C") (pintype "passive"))
      (node (ref "Q7") (pin "3") (pinfunction "C_3") (pintype "passive"))
      (node (ref "T4") (pin "2") (pinfunction "P$2_2") (pintype "passive"))
    )
    (net (code "40") (name "Net-(Q8-B)") (class "Default")
      (node (ref "Q8") (pin "2") (pinfunction "B_2") (pintype "passive"))
      (node (ref "T4") (pin "5") (pinfunction "P$4_5") (pintype "passive"))
    )
    (net (code "41") (name "Net-(Q8-C)") (class "Default")
      (node (ref "Q8") (pin "3") (pinfunction "C_3") (pintype "passive"))
      (node (ref "U$1") (pin "AJ2") (pinfunction "1_AJ2") (pintype "bidirectional"))
    )
    (net (code "42") (name "Net-(Q8-E)") (class "Default")
      (node (ref "D32") (pin "C") (pinfunction "C_C") (pintype "passive"))
      (node (ref "Q8") (pin "1") (pinfunction "E_1") (pintype "passive"))
      (node (ref "T4") (pin "4") (pinfunction "P$5_4") (pintype "passive"))
      (node (ref "U$1") (pin "AK2") (pinfunction "1_AK2") (pintype "bidirectional"))
    )
    (net (code "43") (name "Net-(Q9-B)") (class "Default")
      (node (ref "D36") (pin "A") (pinfunction "A_A") (pintype "passive"))
      (node (ref "Q9") (pin "2") (pinfunction "B_2") (pintype "passive"))
      (node (ref "R26") (pin "1") (pinfunction "1_1") (pintype "passive"))
    )
    (net (code "44") (name "Net-(Q9-C)") (class "Default")
      (node (ref "D38") (pin "C") (pinfunction "C_C") (pintype "passive"))
      (node (ref "Q9") (pin "3") (pinfunction "C_3") (pintype "passive"))
      (node (ref "T5") (pin "2") (pinfunction "P$2_2") (pintype "passive"))
    )
    (net (code "45") (name "Net-(Q10-B)") (class "Default")
      (node (ref "Q10") (pin "2") (pinfunction "B_2") (pintype "passive"))
      (node (ref "T5") (pin "5") (pinfunction "P$4_5") (pintype "passive"))
    )
    (net (code "46") (name "Net-(Q10-C)") (class "Default")
      (node (ref "D39") (pin "A") (pinfunction "A_A") (pintype "passive"))
      (node (ref "Q10") (pin "3") (pinfunction "C_3") (pintype "passive"))
      (node (ref "U$1") (pin "BH2") (pinfunction "1_BH2") (pintype "bidirectional"))
    )
    (net (code "47") (name "Net-(Q10-E)") (class "Default")
      (node (ref "Q10") (pin "1") (pinfunction "E_1") (pintype "passive"))
      (node (ref "T5") (pin "4") (pinfunction "P$5_4") (pintype "passive"))
      (node (ref "U$1") (pin "BF2") (pinfunction "1_BF2") (pintype "bidirectional"))
    )
    (net (code "48") (name "Net-(Q11-B)") (class "Default")
      (node (ref "D44") (pin "A") (pinfunction "A_A") (pintype "passive"))
      (node (ref "Q11") (pin "2") (pinfunction "B_2") (pintype "passive"))
      (node (ref "R32") (pin "1") (pinfunction "1_1") (pintype "passive"))
    )
    (net (code "49") (name "Net-(Q11-C)") (class "Default")
      (node (ref "D46") (pin "C") (pinfunction "C_C") (pintype "passive"))
      (node (ref "Q11") (pin "3") (pinfunction "C_3") (pintype "passive"))
      (node (ref "T6") (pin "2") (pinfunction "P$2_2") (pintype "passive"))
    )
    (net (code "50") (name "Net-(Q12-B)") (class "Default")
      (node (ref "Q12") (pin "2") (pinfunction "B_2") (pintype "passive"))
      (node (ref "T6") (pin "5") (pinfunction "P$4_5") (pintype "passive"))
    )
    (net (code "51") (name "Net-(Q12-C)") (class "Default")
      (node (ref "D47") (pin "A") (pinfunction "A_A") (pintype "passive"))
      (node (ref "Q12") (pin "3") (pinfunction "C_3") (pintype "passive"))
      (node (ref "U$1") (pin "BM2") (pinfunction "1_BM2") (pintype "bidirectional"))
    )
    (net (code "52") (name "Net-(Q12-E)") (class "Default")
      (node (ref "Q12") (pin "1") (pinfunction "E_1") (pintype "passive"))
      (node (ref "T6") (pin "4") (pinfunction "P$5_4") (pintype "passive"))
      (node (ref "U$1") (pin "BL2") (pinfunction "1_BL2") (pintype "bidirectional"))
    )
    (net (code "53") (name "Net-(Q13-B)") (class "Default")
      (node (ref "D52") (pin "A") (pinfunction "A_A") (pintype "passive"))
      (node (ref "Q13") (pin "2") (pinfunction "B_2") (pintype "passive"))
      (node (ref "R38") (pin "1") (pinfunction "1_1") (pintype "passive"))
    )
    (net (code "54") (name "Net-(Q13-C)") (class "Default")
      (node (ref "D54") (pin "C") (pinfunction "C_C") (pintype "passive"))
      (node (ref "Q13") (pin "3") (pinfunction "C_3") (pintype "passive"))
      (node (ref "T9") (pin "7") (pinfunction "P$7_7") (pintype "passive"))
    )
    (net (code "55") (name "Net-(Q14-B)") (class "Default")
      (node (ref "Q14") (pin "2") (pinfunction "B_2") (pintype "passive"))
      (node (ref "T9") (pin "4") (pinfunction "P$5_4") (pintype "passive"))
    )
    (net (code "56") (name "Net-(Q14-C)") (class "Default")
      (node (ref "D55") (pin "A") (pinfunction "A_A") (pintype "passive"))
      (node (ref "Q14") (pin "3") (pinfunction "C_3") (pintype "passive"))
      (node (ref "U$1") (pin "BN2") (pinfunction "1_BN2") (pintype "bidirectional"))
    )
    (net (code "57") (name "Net-(Q14-E)") (class "Default")
      (node (ref "Q14") (pin "1") (pinfunction "E_1") (pintype "passive"))
      (node (ref "T9") (pin "5") (pinfunction "P$4_5") (pintype "passive"))
      (node (ref "U$1") (pin "BP2") (pinfunction "1_BP2") (pintype "bidirectional"))
    )
    (net (code "58") (name "Net-(Q15-B)") (class "Default")
      (node (ref "D60") (pin "A") (pinfunction "A_A") (pintype "passive"))
      (node (ref "Q15") (pin "2") (pinfunction "B_2") (pintype "passive"))
      (node (ref "R44") (pin "1") (pinfunction "1_1") (pintype "passive"))
    )
    (net (code "59") (name "Net-(Q15-C)") (class "Default")
      (node (ref "D62") (pin "C") (pinfunction "C_C") (pintype "passive"))
      (node (ref "Q15") (pin "3") (pinfunction "C_3") (pintype "passive"))
      (node (ref "T8") (pin "2") (pinfunction "P$2_2") (pintype "passive"))
    )
    (net (code "60") (name "Net-(Q16-B)") (class "Default")
      (node (ref "Q16") (pin "2") (pinfunction "B_2") (pintype "passive"))
      (node (ref "T8") (pin "5") (pinfunction "P$4_5") (pintype "passive"))
    )
    (net (code "61") (name "Net-(Q16-C)") (class "Default")
      (node (ref "D63") (pin "A") (pinfunction "A_A") (pintype "passive"))
      (node (ref "Q16") (pin "3") (pinfunction "C_3") (pintype "passive"))
      (node (ref "U$1") (pin "BJ2") (pinfunction "1_BJ2") (pintype "bidirectional"))
    )
    (net (code "62") (name "Net-(Q16-E)") (class "Default")
      (node (ref "Q16") (pin "1") (pinfunction "E_1") (pintype "passive"))
      (node (ref "T8") (pin "4") (pinfunction "P$5_4") (pintype "passive"))
      (node (ref "U$1") (pin "BK2") (pinfunction "1_BK2") (pintype "bidirectional"))
    )
    (net (code "63") (name "Net-(T1-P$7)") (class "Default")
      (node (ref "C1") (pin "1") (pinfunction "1_1") (pintype "passive"))
      (node (ref "R3") (pin "2") (pinfunction "2_2") (pintype "passive"))
      (node (ref "R4") (pin "2") (pinfunction "2_2") (pintype "passive"))
      (node (ref "R5") (pin "2") (pinfunction "2_2") (pintype "passive"))
      (node (ref "R6") (pin "2") (pinfunction "2_2") (pintype "passive"))
      (node (ref "T1") (pin "7") (pinfunction "P$7_7") (pintype "passive"))
    )
    (net (code "64") (name "Net-(T2-P$7)") (class "Default")
      (node (ref "C2") (pin "1") (pinfunction "1_1") (pintype "passive"))
      (node (ref "R10") (pin "2") (pinfunction "2_2") (pintype "passive"))
      (node (ref "R11") (pin "2") (pinfunction "2_2") (pintype "passive"))
      (node (ref "R12") (pin "2") (pinfunction "2_2") (pintype "passive"))
      (node (ref "R13") (pin "2") (pinfunction "2_2") (pintype "passive"))
      (node (ref "T2") (pin "7") (pinfunction "P$7_7") (pintype "passive"))
    )
    (net (code "65") (name "Net-(T3-P$2)") (class "Default")
      (node (ref "C5") (pin "1") (pinfunction "1_1") (pintype "passive"))
      (node (ref "R16") (pin "2") (pinfunction "2_2") (pintype "passive"))
      (node (ref "R17") (pin "2") (pinfunction "2_2") (pintype "passive"))
      (node (ref "R18") (pin "2") (pinfunction "2_2") (pintype "passive"))
      (node (ref "R19") (pin "2") (pinfunction "2_2") (pintype "passive"))
      (node (ref "T3") (pin "2") (pinfunction "P$2_2") (pintype "passive"))
    )
    (net (code "66") (name "Net-(T4-P$7)") (class "Default")
      (node (ref "C6") (pin "1") (pinfunction "1_1") (pintype "passive"))
      (node (ref "R22") (pin "2") (pinfunction "2_2") (pintype "passive"))
      (node (ref "R23") (pin "2") (pinfunction "2_2") (pintype "passive"))
      (node (ref "R24") (pin "2") (pinfunction "2_2") (pintype "passive"))
      (node (ref "R25") (pin "2") (pinfunction "2_2") (pintype "passive"))
      (node (ref "T4") (pin "7") (pinfunction "P$7_7") (pintype "passive"))
    )
    (net (code "67") (name "Net-(T5-P$7)") (class "Default")
      (node (ref "C7") (pin "1") (pinfunction "1_1") (pintype "passive"))
      (node (ref "R27") (pin "2") (pinfunction "2_2") (pintype "passive"))
      (node (ref "R28") (pin "2") (pinfunction "2_2") (pintype "passive"))
      (node (ref "R29") (pin "2") (pinfunction "2_2") (pintype "passive"))
      (node (ref "R30") (pin "2") (pinfunction "2_2") (pintype "passive"))
      (node (ref "T5") (pin "7") (pinfunction "P$7_7") (pintype "passive"))
    )
    (net (code "68") (name "Net-(T6-P$7)") (class "Default")
      (node (ref "C8") (pin "1") (pinfunction "1_1") (pintype "passive"))
      (node (ref "R33") (pin "2") (pinfunction "2_2") (pintype "passive"))
      (node (ref "R34") (pin "2") (pinfunction "2_2") (pintype "passive"))
      (node (ref "R35") (pin "2") (pinfunction "2_2") (pintype "passive"))
      (node (ref "R36") (pin "2") (pinfunction "2_2") (pintype "passive"))
      (node (ref "T6") (pin "7") (pinfunction "P$7_7") (pintype "passive"))
    )
    (net (code "69") (name "Net-(T8-P$7)") (class "Default")
      (node (ref "C10") (pin "1") (pinfunction "1_1") (pintype "passive"))
      (node (ref "R45") (pin "2") (pinfunction "2_2") (pintype "passive"))
      (node (ref "R46") (pin "2") (pinfunction "2_2") (pintype "passive"))
      (node (ref "R47") (pin "2") (pinfunction "2_2") (pintype "passive"))
      (node (ref "R48") (pin "2") (pinfunction "2_2") (pintype "passive"))
      (node (ref "T8") (pin "7") (pinfunction "P$7_7") (pintype "passive"))
    )
    (net (code "70") (name "Net-(T9-P$2)") (class "Default")
      (node (ref "C9") (pin "1") (pinfunction "1_1") (pintype "passive"))
      (node (ref "R39") (pin "2") (pinfunction "2_2") (pintype "passive"))
      (node (ref "R40") (pin "2") (pinfunction "2_2") (pintype "passive"))
      (node (ref "R41") (pin "2") (pinfunction "2_2") (pintype "passive"))
      (node (ref "R42") (pin "2") (pinfunction "2_2") (pintype "passive"))
      (node (ref "T9") (pin "2") (pinfunction "P$2_2") (pintype "passive"))
    )
    (net (code "71") (name "Net-(U$1AB-1)") (class "Default")
      (node (ref "C13") (pin "-") (pinfunction "-_-") (pintype "passive"))
      (node (ref "C14") (pin "+") (pinfunction "+_+") (pintype "passive"))
      (node (ref "D16") (pin "A") (pinfunction "A_A") (pintype "passive"))
      (node (ref "D24") (pin "A") (pinfunction "A_A") (pintype "passive"))
      (node (ref "D32") (pin "A") (pinfunction "A_A") (pintype "passive"))
      (node (ref "D6") (pin "A") (pinfunction "A_A") (pintype "passive"))
      (node (ref "U$1") (pin "AR2") (pinfunction "1_AR2") (pintype "bidirectional"))
    )
    (net (code "72") (name "Net-(U$1AD-1)") (class "Default")
      (node (ref "D12") (pin "A") (pinfunction "A_A") (pintype "passive"))
      (node (ref "D13") (pin "A") (pinfunction "A_A") (pintype "passive"))
      (node (ref "U$1") (pin "AS2") (pinfunction "1_AS2") (pintype "bidirectional"))
    )
    (net (code "73") (name "Net-(U$1AF-1)") (class "Default")
      (node (ref "D22") (pin "A") (pinfunction "A_A") (pintype "passive"))
      (node (ref "D30") (pin "A") (pinfunction "A_A") (pintype "passive"))
      (node (ref "U$1") (pin "AT2") (pinfunction "1_AT2") (pintype "bidirectional"))
    )
    (net (code "74") (name "Net-(U$1AH-1)") (class "Default")
      (node (ref "D1") (pin "A") (pinfunction "A_A") (pintype "passive"))
      (node (ref "D18") (pin "A") (pinfunction "A_A") (pintype "passive"))
      (node (ref "D26") (pin "A") (pinfunction "A_A") (pintype "passive"))
      (node (ref "D8") (pin "A") (pinfunction "A_A") (pintype "passive"))
      (node (ref "U$1") (pin "AU2") (pinfunction "1_AU2") (pintype "bidirectional"))
    )
    (net (code "75") (name "Net-(U$1AJ-1)") (class "Default")
      (node (ref "D19") (pin "A") (pinfunction "A_A") (pintype "passive"))
      (node (ref "D2") (pin "A") (pinfunction "A_A") (pintype "passive"))
      (node (ref "D27") (pin "A") (pinfunction "A_A") (pintype "passive"))
      (node (ref "D9") (pin "A") (pinfunction "A_A") (pintype "passive"))
      (node (ref "U$1") (pin "AV2") (pinfunction "1_AV2") (pintype "bidirectional"))
    )
    (net (code "76") (name "Net-(U$1AR-1)") (class "Default")
      (node (ref "D40") (pin "A") (pinfunction "A_A") (pintype "passive"))
      (node (ref "D64") (pin "A") (pinfunction "A_A") (pintype "passive"))
      (node (ref "U$1") (pin "BD2") (pinfunction "1_BD2") (pintype "bidirectional"))
    )
    (net (code "77") (name "Net-(U$1AT-1)") (class "Default")
      (node (ref "D48") (pin "A") (pinfunction "A_A") (pintype "passive"))
      (node (ref "D56") (pin "A") (pinfunction "A_A") (pintype "passive"))
      (node (ref "U$1") (pin "BE2") (pinfunction "1_BE2") (pintype "bidirectional"))
    )
    (net (code "78") (name "Net-(U$1BL-1)") (class "Default")
      (node (ref "C13") (pin "+") (pinfunction "+_+") (pintype "passive"))
      (node (ref "C15") (pin "+") (pinfunction "+_+") (pintype "passive"))
      (node (ref "D39") (pin "C") (pinfunction "C_C") (pintype "passive"))
      (node (ref "D47") (pin "C") (pinfunction "C_C") (pintype "passive"))
      (node (ref "D55") (pin "C") (pinfunction "C_C") (pintype "passive"))
      (node (ref "D63") (pin "C") (pinfunction "C_C") (pintype "passive"))
      (node (ref "U$1") (pin "BR2") (pinfunction "1_BR2") (pintype "bidirectional"))
    )
    (net (code "79") (name "Net-(U$1BN-1)") (class "Default")
      (node (ref "D37") (pin "A") (pinfunction "A_A") (pintype "passive"))
      (node (ref "D45") (pin "A") (pinfunction "A_A") (pintype "passive"))
      (node (ref "U$1") (pin "BS2") (pinfunction "1_BS2") (pintype "bidirectional"))
    )
    (net (code "80") (name "Net-(U$1BP-1)") (class "Default")
      (node (ref "D53") (pin "A") (pinfunction "A_A") (pintype "passive"))
      (node (ref "D61") (pin "A") (pinfunction "A_A") (pintype "passive"))
      (node (ref "U$1") (pin "BT2") (pinfunction "1_BT2") (pintype "bidirectional"))
    )
    (net (code "81") (name "Net-(U$1BR-1)") (class "Default")
      (node (ref "D15") (pin "A") (pinfunction "A_A") (pintype "passive"))
      (node (ref "D41") (pin "A") (pinfunction "A_A") (pintype "passive"))
      (node (ref "D49") (pin "A") (pinfunction "A_A") (pintype "passive"))
      (node (ref "D57") (pin "A") (pinfunction "A_A") (pintype "passive"))
      (node (ref "U$1") (pin "BU2") (pinfunction "1_BU2") (pintype "bidirectional"))
    )
    (net (code "82") (name "Net-(U$1BT-1)") (class "Default")
      (node (ref "D34") (pin "A") (pinfunction "A_A") (pintype "passive"))
      (node (ref "D42") (pin "A") (pinfunction "A_A") (pintype "passive"))
      (node (ref "D50") (pin "A") (pinfunction "A_A") (pintype "passive"))
      (node (ref "D58") (pin "A") (pinfunction "A_A") (pintype "passive"))
      (node (ref "U$1") (pin "BV2") (pinfunction "1_BV2") (pintype "bidirectional"))
    )
    (net (code "83") (name "Net-(U$1H-1)") (class "Default")
      (node (ref "D33") (pin "A") (pinfunction "A_A") (pintype "passive"))
      (node (ref "D7") (pin "A") (pinfunction "A_A") (pintype "passive"))
      (node (ref "U$1") (pin "AD2") (pinfunction "1_AD2") (pintype "bidirectional"))
    )
    (net (code "84") (name "Net-(U$1J-1)") (class "Default")
      (node (ref "D17") (pin "A") (pinfunction "A_A") (pintype "passive"))
      (node (ref "D25") (pin "A") (pinfunction "A_A") (pintype "passive"))
      (node (ref "U$1") (pin "AE2") (pinfunction "1_AE2") (pintype "bidirectional"))
    )
  )
)
